# smith_corona.net
KiCad netlist of a schematic drawn in EAGLE
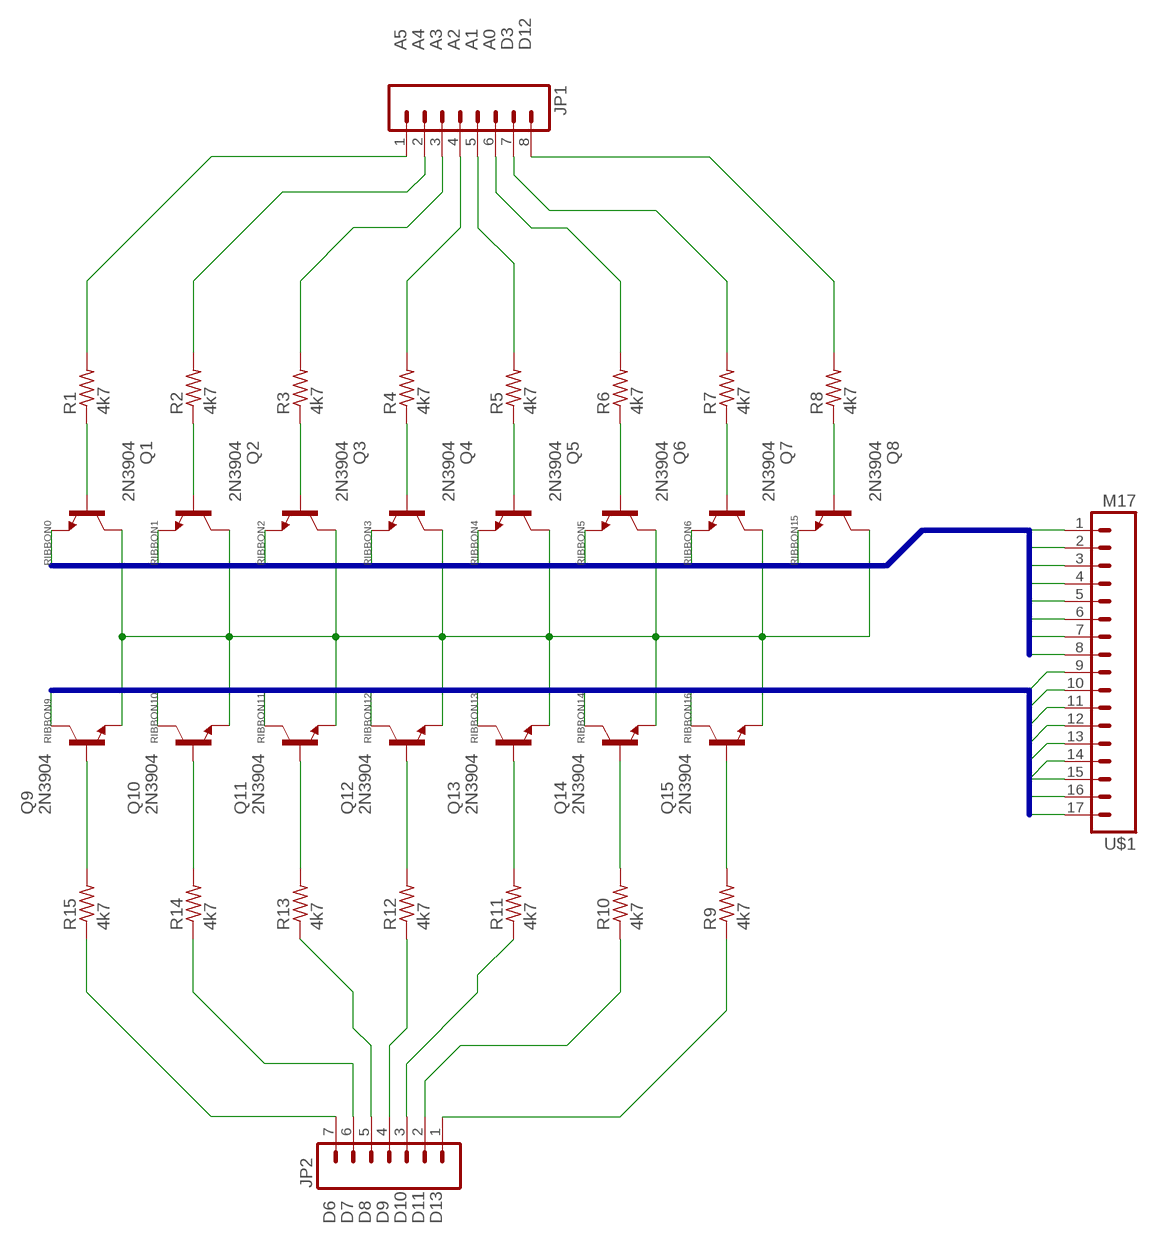
[diagram p0: schematic, sheet 1]

(export (version "E")
  (design (tool "Eeschema 10.0.6"))
  (components
    (comp (ref "JP1")
      (value "M08LONGPADS")
      (footprint "eagle-import:1X08_LONGPADS")
      (libsource (lib "eagle-import") (part "M08LONGPADS"))
    )
    (comp (ref "JP2")
      (value "M07LONGPADS")
      (footprint "eagle-import:1X07_LONGPADS")
      (libsource (lib "eagle-import") (part "M07LONGPADS"))
    )
    (comp (ref "Q1")
      (value "2N3904")
      (footprint "eagle-import:TO92")
      (libsource (lib "eagle-import") (part "2N3904"))
    )
    (comp (ref "Q2")
      (value "2N3904")
      (footprint "eagle-import:TO92")
      (libsource (lib "eagle-import") (part "2N3904"))
    )
    (comp (ref "Q3")
      (value "2N3904")
      (footprint "eagle-import:TO92")
      (libsource (lib "eagle-import") (part "2N3904"))
    )
    (comp (ref "Q4")
      (value "2N3904")
      (footprint "eagle-import:TO92")
      (libsource (lib "eagle-import") (part "2N3904"))
    )
    (comp (ref "Q5")
      (value "2N3904")
      (footprint "eagle-import:TO92")
      (libsource (lib "eagle-import") (part "2N3904"))
    )
    (comp (ref "Q6")
      (value "2N3904")
      (footprint "eagle-import:TO92")
      (libsource (lib "eagle-import") (part "2N3904"))
    )
    (comp (ref "Q7")
      (value "2N3904")
      (footprint "eagle-import:TO92")
      (libsource (lib "eagle-import") (part "2N3904"))
    )
    (comp (ref "Q8")
      (value "2N3904")
      (footprint "eagle-import:TO92")
      (libsource (lib "eagle-import") (part "2N3904"))
    )
    (comp (ref "Q9")
      (value "2N3904")
      (footprint "eagle-import:TO92")
      (libsource (lib "eagle-import") (part "2N3904"))
    )
    (comp (ref "Q10")
      (value "2N3904")
      (footprint "eagle-import:TO92")
      (libsource (lib "eagle-import") (part "2N3904"))
    )
    (comp (ref "Q11")
      (value "2N3904")
      (footprint "eagle-import:TO92")
      (libsource (lib "eagle-import") (part "2N3904"))
    )
    (comp (ref "Q12")
      (value "2N3904")
      (footprint "eagle-import:TO92")
      (libsource (lib "eagle-import") (part "2N3904"))
    )
    (comp (ref "Q13")
      (value "2N3904")
      (footprint "eagle-import:TO92")
      (libsource (lib "eagle-import") (part "2N3904"))
    )
    (comp (ref "Q14")
      (value "2N3904")
      (footprint "eagle-import:TO92")
      (libsource (lib "eagle-import") (part "2N3904"))
    )
    (comp (ref "Q15")
      (value "2N3904")
      (footprint "eagle-import:TO92")
      (libsource (lib "eagle-import") (part "2N3904"))
    )
    (comp (ref "R1")
      (value "4k7")
      (footprint "eagle-import:0207_10")
      (libsource (lib "eagle-import") (part "R-US_0207/10"))
    )
    (comp (ref "R2")
      (value "4k7")
      (footprint "eagle-import:0207_10")
      (libsource (lib "eagle-import") (part "R-US_0207/10"))
    )
    (comp (ref "R3")
      (value "4k7")
      (footprint "eagle-import:0207_10")
      (libsource (lib "eagle-import") (part "R-US_0207/10"))
    )
    (comp (ref "R4")
      (value "4k7")
      (footprint "eagle-import:0207_10")
      (libsource (lib "eagle-import") (part "R-US_0207/10"))
    )
    (comp (ref "R5")
      (value "4k7")
      (footprint "eagle-import:0207_10")
      (libsource (lib "eagle-import") (part "R-US_0207/10"))
    )
    (comp (ref "R6")
      (value "4k7")
      (footprint "eagle-import:0207_10")
      (libsource (lib "eagle-import") (part "R-US_0207/10"))
    )
    (comp (ref "R7")
      (value "4k7")
      (footprint "eagle-import:0207_10")
      (libsource (lib "eagle-import") (part "R-US_0207/10"))
    )
    (comp (ref "R8")
      (value "4k7")
      (footprint "eagle-import:0207_10")
      (libsource (lib "eagle-import") (part "R-US_0207/10"))
    )
    (comp (ref "R9")
      (value "4k7")
      (footprint "eagle-import:0207_10")
      (libsource (lib "eagle-import") (part "R-US_0207/10"))
    )
    (comp (ref "R10")
      (value "4k7")
      (footprint "eagle-import:0207_10")
      (libsource (lib "eagle-import") (part "R-US_0207/10"))
    )
    (comp (ref "R11")
      (value "4k7")
      (footprint "eagle-import:0207_10")
      (libsource (lib "eagle-import") (part "R-US_0207/10"))
    )
    (comp (ref "R12")
      (value "4k7")
      (footprint "eagle-import:0207_10")
      (libsource (lib "eagle-import") (part "R-US_0207/10"))
    )
    (comp (ref "R13")
      (value "4k7")
      (footprint "eagle-import:0207_10")
      (libsource (lib "eagle-import") (part "R-US_0207/10"))
    )
    (comp (ref "R14")
      (value "4k7")
      (footprint "eagle-import:0207_10")
      (libsource (lib "eagle-import") (part "R-US_0207/10"))
    )
    (comp (ref "R15")
      (value "4k7")
      (footprint "eagle-import:0207_10")
      (libsource (lib "eagle-import") (part "R-US_0207/10"))
    )
    (comp (ref "U$1")
      (value "M17")
      (footprint "eagle-import:1X17")
      (libsource (lib "eagle-import") (part "M17"))
    )
  )
  (nets
    (net (code "3") (name "/RIBBON[0..16]") (class "Default")
      (node (ref "U$1") (pin "8") (pinfunction "8_8") (pintype "passive"))
    )
    (net (code "4") (name "Net-(JP1-Pad1)") (class "Default")
      (node (ref "JP1") (pin "1") (pinfunction "1_1") (pintype "passive"))
      (node (ref "R1") (pin "2") (pinfunction "2_2") (pintype "passive"))
    )
    (net (code "5") (name "Net-(JP1-Pad2)") (class "Default")
      (node (ref "JP1") (pin "2") (pinfunction "2_2") (pintype "passive"))
      (node (ref "R2") (pin "2") (pinfunction "2_2") (pintype "passive"))
    )
    (net (code "6") (name "Net-(JP1-Pad3)") (class "Default")
      (node (ref "JP1") (pin "3") (pinfunction "3_3") (pintype "passive"))
      (node (ref "R3") (pin "2") (pinfunction "2_2") (pintype "passive"))
    )
    (net (code "7") (name "Net-(JP1-Pad4)") (class "Default")
      (node (ref "JP1") (pin "4") (pinfunction "4_4") (pintype "passive"))
      (node (ref "R4") (pin "2") (pinfunction "2_2") (pintype "passive"))
    )
    (net (code "8") (name "Net-(JP1-Pad5)") (class "Default")
      (node (ref "JP1") (pin "5") (pinfunction "5_5") (pintype "passive"))
      (node (ref "R5") (pin "2") (pinfunction "2_2") (pintype "passive"))
    )
    (net (code "9") (name "Net-(JP1-Pad6)") (class "Default")
      (node (ref "JP1") (pin "6") (pinfunction "6_6") (pintype "passive"))
      (node (ref "R6") (pin "2") (pinfunction "2_2") (pintype "passive"))
    )
    (net (code "10") (name "Net-(JP1-Pad7)") (class "Default")
      (node (ref "JP1") (pin "7") (pinfunction "7_7") (pintype "passive"))
      (node (ref "R7") (pin "2") (pinfunction "2_2") (pintype "passive"))
    )
    (net (code "11") (name "Net-(JP1-Pad8)") (class "Default")
      (node (ref "JP1") (pin "8") (pinfunction "8_8") (pintype "passive"))
      (node (ref "R8") (pin "2") (pinfunction "2_2") (pintype "passive"))
    )
    (net (code "12") (name "Net-(JP2-Pad1)") (class "Default")
      (node (ref "JP2") (pin "1") (pinfunction "1_1") (pintype "passive"))
      (node (ref "R9") (pin "1") (pinfunction "1_1") (pintype "passive"))
    )
    (net (code "13") (name "Net-(JP2-Pad2)") (class "Default")
      (node (ref "JP2") (pin "2") (pinfunction "2_2") (pintype "passive"))
      (node (ref "R10") (pin "1") (pinfunction "1_1") (pintype "passive"))
    )
    (net (code "14") (name "Net-(JP2-Pad3)") (class "Default")
      (node (ref "JP2") (pin "3") (pinfunction "3_3") (pintype "passive"))
      (node (ref "R11") (pin "1") (pinfunction "1_1") (pintype "passive"))
    )
    (net (code "15") (name "Net-(JP2-Pad4)") (class "Default")
      (node (ref "JP2") (pin "4") (pinfunction "4_4") (pintype "passive"))
      (node (ref "R12") (pin "1") (pinfunction "1_1") (pintype "passive"))
    )
    (net (code "16") (name "Net-(JP2-Pad5)") (class "Default")
      (node (ref "JP2") (pin "5") (pinfunction "5_5") (pintype "passive"))
      (node (ref "R13") (pin "1") (pinfunction "1_1") (pintype "passive"))
    )
    (net (code "17") (name "Net-(JP2-Pad6)") (class "Default")
      (node (ref "JP2") (pin "6") (pinfunction "6_6") (pintype "passive"))
      (node (ref "R14") (pin "1") (pinfunction "1_1") (pintype "passive"))
    )
    (net (code "18") (name "Net-(JP2-Pad7)") (class "Default")
      (node (ref "JP2") (pin "7") (pinfunction "7_7") (pintype "passive"))
      (node (ref "R15") (pin "1") (pinfunction "1_1") (pintype "passive"))
    )
    (net (code "19") (name "Net-(Q1-B)") (class "Default")
      (node (ref "Q1") (pin "2") (pinfunction "B_2") (pintype "passive"))
      (node (ref "R1") (pin "1") (pinfunction "1_1") (pintype "passive"))
    )
    (net (code "20") (name "Net-(Q1-C)") (class "Default")
      (node (ref "Q1") (pin "1") (pinfunction "C_1") (pintype "passive"))
      (node (ref "Q10") (pin "3") (pinfunction "E_3") (pintype "passive"))
      (node (ref "Q11") (pin "3") (pinfunction "E_3") (pintype "passive"))
      (node (ref "Q12") (pin "3") (pinfunction "E_3") (pintype "passive"))
      (node (ref "Q13") (pin "3") (pinfunction "E_3") (pintype "passive"))
      (node (ref "Q14") (pin "3") (pinfunction "E_3") (pintype "passive"))
      (node (ref "Q15") (pin "3") (pinfunction "E_3") (pintype "passive"))
      (node (ref "Q2") (pin "1") (pinfunction "C_1") (pintype "passive"))
      (node (ref "Q3") (pin "1") (pinfunction "C_1") (pintype "passive"))
      (node (ref "Q4") (pin "1") (pinfunction "C_1") (pintype "passive"))
      (node (ref "Q5") (pin "1") (pinfunction "C_1") (pintype "passive"))
      (node (ref "Q6") (pin "1") (pinfunction "C_1") (pintype "passive"))
      (node (ref "Q7") (pin "1") (pinfunction "C_1") (pintype "passive"))
      (node (ref "Q8") (pin "1") (pinfunction "C_1") (pintype "passive"))
      (node (ref "Q9") (pin "3") (pinfunction "E_3") (pintype "passive"))
    )
    (net (code "21") (name "Net-(Q2-B)") (class "Default")
      (node (ref "Q2") (pin "2") (pinfunction "B_2") (pintype "passive"))
      (node (ref "R2") (pin "1") (pinfunction "1_1") (pintype "passive"))
    )
    (net (code "22") (name "Net-(Q3-B)") (class "Default")
      (node (ref "Q3") (pin "2") (pinfunction "B_2") (pintype "passive"))
      (node (ref "R3") (pin "1") (pinfunction "1_1") (pintype "passive"))
    )
    (net (code "23") (name "Net-(Q4-B)") (class "Default")
      (node (ref "Q4") (pin "2") (pinfunction "B_2") (pintype "passive"))
      (node (ref "R4") (pin "1") (pinfunction "1_1") (pintype "passive"))
    )
    (net (code "24") (name "Net-(Q5-B)") (class "Default")
      (node (ref "Q5") (pin "2") (pinfunction "B_2") (pintype "passive"))
      (node (ref "R5") (pin "1") (pinfunction "1_1") (pintype "passive"))
    )
    (net (code "25") (name "Net-(Q6-B)") (class "Default")
      (node (ref "Q6") (pin "2") (pinfunction "B_2") (pintype "passive"))
      (node (ref "R6") (pin "1") (pinfunction "1_1") (pintype "passive"))
    )
    (net (code "26") (name "Net-(Q7-B)") (class "Default")
      (node (ref "Q7") (pin "2") (pinfunction "B_2") (pintype "passive"))
      (node (ref "R7") (pin "1") (pinfunction "1_1") (pintype "passive"))
    )
    (net (code "27") (name "Net-(Q8-B)") (class "Default")
      (node (ref "Q8") (pin "2") (pinfunction "B_2") (pintype "passive"))
      (node (ref "R8") (pin "1") (pinfunction "1_1") (pintype "passive"))
    )
    (net (code "28") (name "Net-(Q9-B)") (class "Default")
      (node (ref "Q9") (pin "2") (pinfunction "B_2") (pintype "passive"))
      (node (ref "R15") (pin "2") (pinfunction "2_2") (pintype "passive"))
    )
    (net (code "29") (name "Net-(Q10-B)") (class "Default")
      (node (ref "Q10") (pin "2") (pinfunction "B_2") (pintype "passive"))
      (node (ref "R14") (pin "2") (pinfunction "2_2") (pintype "passive"))
    )
    (net (code "30") (name "Net-(Q11-B)") (class "Default")
      (node (ref "Q11") (pin "2") (pinfunction "B_2") (pintype "passive"))
      (node (ref "R13") (pin "2") (pinfunction "2_2") (pintype "passive"))
    )
    (net (code "31") (name "Net-(Q12-B)") (class "Default")
      (node (ref "Q12") (pin "2") (pinfunction "B_2") (pintype "passive"))
      (node (ref "R12") (pin "2") (pinfunction "2_2") (pintype "passive"))
    )
    (net (code "32") (name "Net-(Q13-B)") (class "Default")
      (node (ref "Q13") (pin "2") (pinfunction "B_2") (pintype "passive"))
      (node (ref "R11") (pin "2") (pinfunction "2_2") (pintype "passive"))
    )
    (net (code "33") (name "Net-(Q14-B)") (class "Default")
      (node (ref "Q14") (pin "2") (pinfunction "B_2") (pintype "passive"))
      (node (ref "R10") (pin "2") (pinfunction "2_2") (pintype "passive"))
    )
    (net (code "34") (name "Net-(Q15-B)") (class "Default")
      (node (ref "Q15") (pin "2") (pinfunction "B_2") (pintype "passive"))
      (node (ref "R9") (pin "2") (pinfunction "2_2") (pintype "passive"))
    )
    (net (code "35") (name "RIBBON0") (class "Default")
      (node (ref "Q1") (pin "3") (pinfunction "E_3") (pintype "passive"))
      (node (ref "U$1") (pin "1") (pinfunction "1_1") (pintype "passive"))
    )
    (net (code "36") (name "RIBBON1") (class "Default")
      (node (ref "Q2") (pin "3") (pinfunction "E_3") (pintype "passive"))
      (node (ref "U$1") (pin "2") (pinfunction "2_2") (pintype "passive"))
    )
    (net (code "37") (name "RIBBON2") (class "Default")
      (node (ref "Q3") (pin "3") (pinfunction "E_3") (pintype "passive"))
      (node (ref "U$1") (pin "3") (pinfunction "3_3") (pintype "passive"))
    )
    (net (code "38") (name "RIBBON3") (class "Default")
      (node (ref "Q4") (pin "3") (pinfunction "E_3") (pintype "passive"))
      (node (ref "U$1") (pin "4") (pinfunction "4_4") (pintype "passive"))
    )
    (net (code "39") (name "RIBBON4") (class "Default")
      (node (ref "Q5") (pin "3") (pinfunction "E_3") (pintype "passive"))
      (node (ref "U$1") (pin "5") (pinfunction "5_5") (pintype "passive"))
    )
    (net (code "40") (name "RIBBON5") (class "Default")
      (node (ref "Q6") (pin "3") (pinfunction "E_3") (pintype "passive"))
      (node (ref "U$1") (pin "6") (pinfunction "6_6") (pintype "passive"))
    )
    (net (code "41") (name "RIBBON6") (class "Default")
      (node (ref "Q7") (pin "3") (pinfunction "E_3") (pintype "passive"))
      (node (ref "U$1") (pin "7") (pinfunction "7_7") (pintype "passive"))
    )
    (net (code "42") (name "RIBBON9") (class "Default")
      (node (ref "Q9") (pin "1") (pinfunction "C_1") (pintype "passive"))
      (node (ref "U$1") (pin "10") (pinfunction "10_10") (pintype "passive"))
    )
    (net (code "43") (name "RIBBON10") (class "Default")
      (node (ref "Q10") (pin "1") (pinfunction "C_1") (pintype "passive"))
      (node (ref "U$1") (pin "11") (pinfunction "11_11") (pintype "passive"))
    )
    (net (code "44") (name "RIBBON11") (class "Default")
      (node (ref "Q11") (pin "1") (pinfunction "C_1") (pintype "passive"))
      (node (ref "U$1") (pin "12") (pinfunction "12_12") (pintype "passive"))
    )
    (net (code "45") (name "RIBBON12") (class "Default")
      (node (ref "Q12") (pin "1") (pinfunction "C_1") (pintype "passive"))
      (node (ref "U$1") (pin "13") (pinfunction "13_13") (pintype "passive"))
    )
    (net (code "46") (name "RIBBON13") (class "Default")
      (node (ref "Q13") (pin "1") (pinfunction "C_1") (pintype "passive"))
      (node (ref "U$1") (pin "14") (pinfunction "14_14") (pintype "passive"))
    )
    (net (code "47") (name "RIBBON14") (class "Default")
      (node (ref "Q14") (pin "1") (pinfunction "C_1") (pintype "passive"))
      (node (ref "U$1") (pin "15") (pinfunction "15_15") (pintype "passive"))
    )
    (net (code "48") (name "RIBBON15") (class "Default")
      (node (ref "Q8") (pin "3") (pinfunction "E_3") (pintype "passive"))
      (node (ref "U$1") (pin "16") (pinfunction "16_16") (pintype "passive"))
    )
    (net (code "49") (name "RIBBON16") (class "Default")
      (node (ref "Q15") (pin "1") (pinfunction "C_1") (pintype "passive"))
      (node (ref "U$1") (pin "17") (pinfunction "17_17") (pintype "passive"))
    )
    (net (code "50") (name "unconnected-(U$1-Pad9)") (class "Default")
      (node (ref "U$1") (pin "9") (pinfunction "9_9") (pintype "passive"))
    )
  )
)
